# IMU.net
KiCad netlist of a schematic drawn in Altium Designer
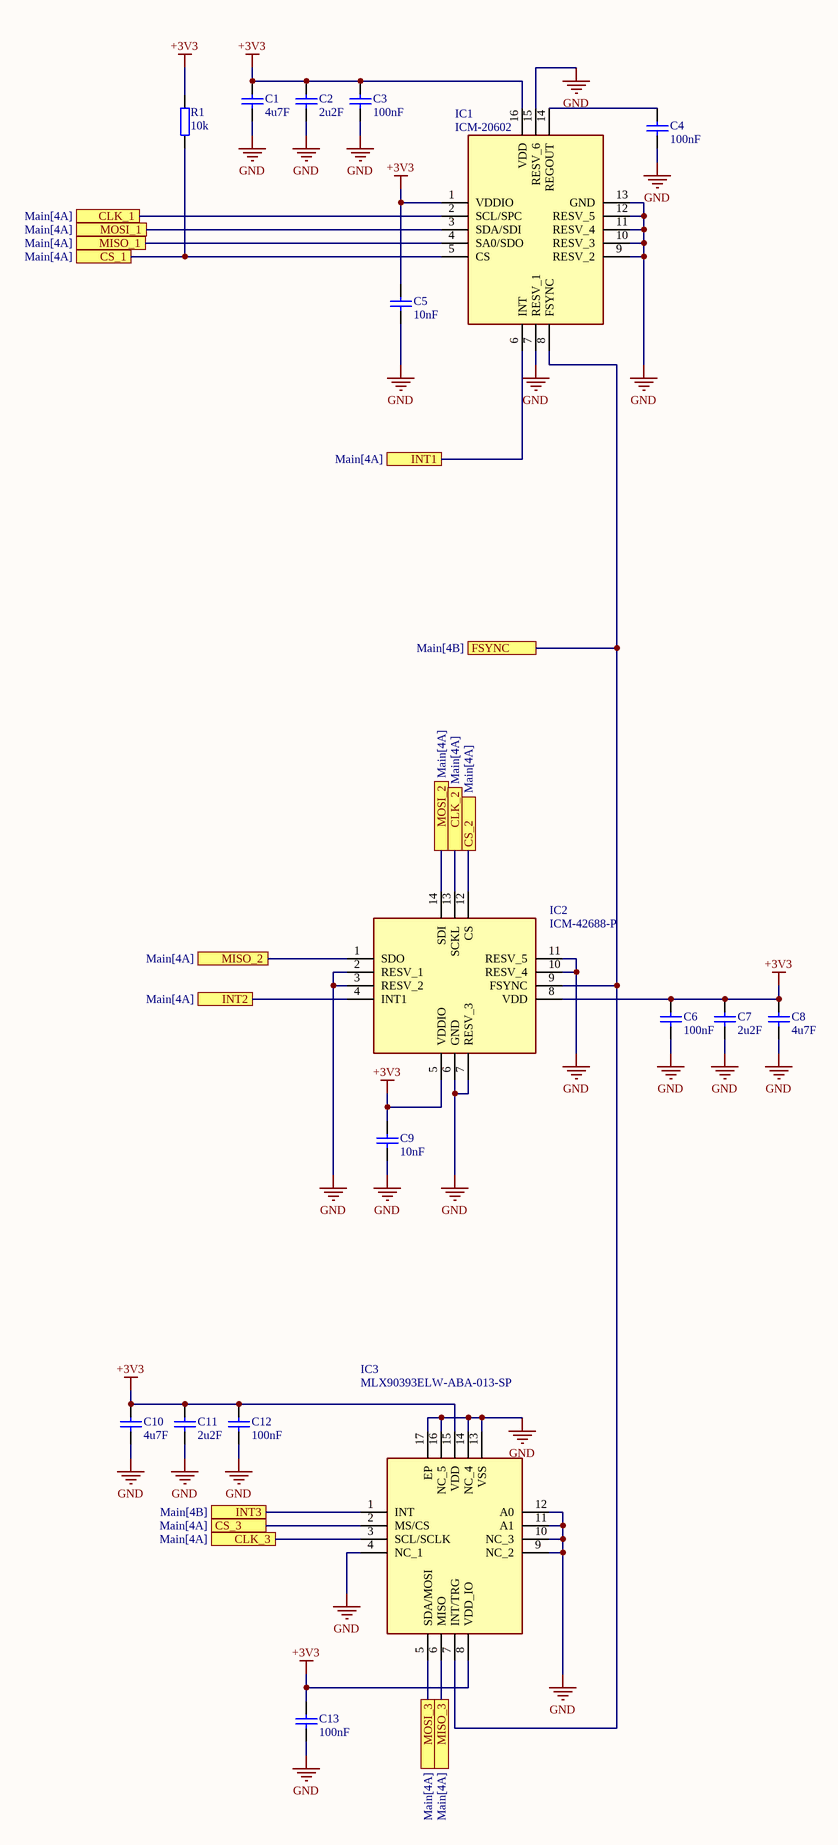
[diagram p0: IMU.SchDoc]

(export (version "E")
  (design (tool "Eeschema 10.0.6"))
  (components
    (comp (ref "C1")
      (value "4u7F")
      (footprint "CAP0805")
      (fields (field (name "VOLTAGE") "35V") (field (name "Comment") "Cap0805"))
      (libsource (lib "capacitorsSMD") (part "Cap0805"))
    )
    (comp (ref "C2")
      (value "2u2F")
      (footprint "CAP0603")
      (fields (field (name "VOLTAGE") "50V") (field (name "Comment") "Cap0603"))
      (libsource (lib "capacitorsSMD") (part "Cap0603"))
    )
    (comp (ref "C3")
      (value "100nF")
      (footprint "CAP0402")
      (fields (field (name "VOLTAGE") "50V") (field (name "Comment") "Cap0402"))
      (libsource (lib "capacitorsSMD") (part "Cap0402"))
    )
    (comp (ref "C4")
      (value "100nF")
      (footprint "CAP0402")
      (fields (field (name "VOLTAGE") "50V") (field (name "Comment") "Cap0402"))
      (libsource (lib "capacitorsSMD") (part "Cap0402"))
    )
    (comp (ref "C5")
      (value "10nF")
      (footprint "CAP0402")
      (fields (field (name "VOLTAGE") "50V") (field (name "Comment") "Cap0402"))
      (libsource (lib "capacitorsSMD") (part "Cap0402"))
    )
    (comp (ref "C6")
      (value "100nF")
      (footprint "CAP0402")
      (fields (field (name "VOLTAGE") "50V") (field (name "Comment") "Cap0402"))
      (libsource (lib "capacitorsSMD") (part "Cap0402"))
    )
    (comp (ref "C7")
      (value "2u2F")
      (footprint "CAP0603")
      (fields (field (name "VOLTAGE") "50V") (field (name "Comment") "Cap0603"))
      (libsource (lib "capacitorsSMD") (part "Cap0603"))
    )
    (comp (ref "C8")
      (value "4u7F")
      (footprint "CAP0805")
      (fields (field (name "VOLTAGE") "35V") (field (name "Comment") "Cap0805"))
      (libsource (lib "capacitorsSMD") (part "Cap0805"))
    )
    (comp (ref "C9")
      (value "10nF")
      (footprint "CAP0402")
      (fields (field (name "VOLTAGE") "50V") (field (name "Comment") "Cap0402"))
      (libsource (lib "capacitorsSMD") (part "Cap0402"))
    )
    (comp (ref "C10")
      (value "4u7F")
      (footprint "CAP0805")
      (fields (field (name "VOLTAGE") "35V") (field (name "Comment") "Cap0805"))
      (libsource (lib "capacitorsSMD") (part "Cap0805"))
    )
    (comp (ref "C11")
      (value "2u2F")
      (footprint "CAP0603")
      (fields (field (name "VOLTAGE") "50V") (field (name "Comment") "Cap0603"))
      (libsource (lib "capacitorsSMD") (part "Cap0603"))
    )
    (comp (ref "C12")
      (value "100nF")
      (footprint "CAP0402")
      (fields (field (name "VOLTAGE") "50V") (field (name "Comment") "Cap0402"))
      (libsource (lib "capacitorsSMD") (part "Cap0402"))
    )
    (comp (ref "C13")
      (value "100nF")
      (footprint "CAP0402")
      (fields (field (name "VOLTAGE") "50V") (field (name "Comment") "Cap0402"))
      (libsource (lib "capacitorsSMD") (part "Cap0402"))
    )
    (comp (ref "IC1")
      (value "ICM-20602")
      (footprint "SamacSys:IAM20680HP")
      (description "Integrated Circuit")
      (fields (field (name "MOUSER PART NUMBER") "410-ICM-20602"))
      (libsource (lib "*") (part "ICM-20602"))
    )
    (comp (ref "IC2")
      (value "ICM-42688-P")
      (footprint "SamacSys:IIM42352")
      (description "Integrated Circuit")
      (fields (field (name "MOUSER PART NUMBER") "410-ICM-42688-P"))
      (libsource (lib "SamacSys") (part "ICM-42688-P"))
    )
    (comp (ref "IC3")
      (value "MLX90393ELW-ABA-013-SP")
      (footprint "SamacSys:QFN50P300X300X100-17N-D")
      (description "Integrated Circuit")
      (fields (field (name "MOUSER PART NUMBER") "482-90393ELWABA013SP"))
      (libsource (lib "*") (part "MLX90393ELW-ABA-013-SP"))
    )
    (comp (ref "R1")
      (value "10k")
      (footprint "RES0402")
      (fields (field (name "Comment") "Res0402"))
      (libsource (lib "resistorSMD") (part "Res0402"))
    )
  )
  (nets
    (net (code "1") (name "+3V3") (class "Default")
      (node (ref "C1") (pin "2") (pinfunction "2_2") (pintype "passive"))
      (node (ref "C10") (pin "2") (pinfunction "2_2") (pintype "passive"))
      (node (ref "C11") (pin "2") (pinfunction "2_2") (pintype "passive"))
      (node (ref "C12") (pin "2") (pinfunction "2_2") (pintype "passive"))
      (node (ref "C13") (pin "2") (pinfunction "2_2") (pintype "passive"))
      (node (ref "C2") (pin "2") (pinfunction "2_2") (pintype "passive"))
      (node (ref "C3") (pin "2") (pinfunction "2_2") (pintype "passive"))
      (node (ref "C5") (pin "2") (pinfunction "2_2") (pintype "passive"))
      (node (ref "C6") (pin "2") (pinfunction "2_2") (pintype "passive"))
      (node (ref "C7") (pin "2") (pinfunction "2_2") (pintype "passive"))
      (node (ref "C8") (pin "2") (pinfunction "2_2") (pintype "passive"))
      (node (ref "C9") (pin "2") (pinfunction "2_2") (pintype "passive"))
      (node (ref "IC1") (pin "1") (pinfunction "VDDIO_1") (pintype "passive"))
      (node (ref "IC1") (pin "16") (pinfunction "VDD_16") (pintype "passive"))
      (node (ref "IC2") (pin "5") (pinfunction "VDDIO_5") (pintype "passive"))
      (node (ref "IC2") (pin "8") (pinfunction "VDD_8") (pintype "passive"))
      (node (ref "IC3") (pin "15") (pinfunction "VDD_15") (pintype "passive"))
      (node (ref "IC3") (pin "8") (pinfunction "VDD_IO_8") (pintype "passive"))
      (node (ref "R1") (pin "2") (pinfunction "2_2") (pintype "passive"))
    )
    (net (code "2") (name "/CLK_1") (class "Default")
      (node (ref "IC1") (pin "2") (pinfunction "SCL/SPC_2") (pintype "passive"))
    )
    (net (code "3") (name "/CLK_2") (class "Default")
      (node (ref "IC2") (pin "13") (pinfunction "SCKL_13") (pintype "passive"))
    )
    (net (code "4") (name "/CLK_3") (class "Default")
      (node (ref "IC3") (pin "3") (pinfunction "SCL/SCLK_3") (pintype "passive"))
    )
    (net (code "5") (name "/CS_1") (class "Default")
      (node (ref "IC1") (pin "5") (pinfunction "CS_5") (pintype "passive"))
      (node (ref "R1") (pin "1") (pinfunction "1_1") (pintype "passive"))
    )
    (net (code "6") (name "/CS_2") (class "Default")
      (node (ref "IC2") (pin "12") (pinfunction "CS_12") (pintype "passive"))
    )
    (net (code "7") (name "/CS_3") (class "Default")
      (node (ref "IC3") (pin "2") (pinfunction "MS/CS_2") (pintype "passive"))
    )
    (net (code "8") (name "/FSYNC") (class "Default")
      (node (ref "IC1") (pin "8") (pinfunction "FSYNC_8") (pintype "passive"))
      (node (ref "IC2") (pin "9") (pinfunction "FSYNC_9") (pintype "passive"))
      (node (ref "IC3") (pin "7") (pinfunction "INT/TRG_7") (pintype "passive"))
    )
    (net (code "9") (name "/INT1") (class "Default")
      (node (ref "IC1") (pin "6") (pinfunction "INT_6") (pintype "passive"))
    )
    (net (code "10") (name "/INT2") (class "Default")
      (node (ref "IC2") (pin "4") (pinfunction "INT1_4") (pintype "passive"))
    )
    (net (code "11") (name "/INT3") (class "Default")
      (node (ref "IC3") (pin "1") (pinfunction "INT_1") (pintype "passive"))
    )
    (net (code "12") (name "/MISO_1") (class "Default")
      (node (ref "IC1") (pin "4") (pinfunction "SA0/SDO_4") (pintype "passive"))
    )
    (net (code "13") (name "/MISO_2") (class "Default")
      (node (ref "IC2") (pin "1") (pinfunction "SDO_1") (pintype "passive"))
    )
    (net (code "14") (name "/MISO_3") (class "Default")
      (node (ref "IC3") (pin "6") (pinfunction "MISO_6") (pintype "passive"))
    )
    (net (code "15") (name "/MOSI_1") (class "Default")
      (node (ref "IC1") (pin "3") (pinfunction "SDA/SDI_3") (pintype "passive"))
    )
    (net (code "16") (name "/MOSI_2") (class "Default")
      (node (ref "IC2") (pin "14") (pinfunction "SDI_14") (pintype "passive"))
    )
    (net (code "17") (name "/MOSI_3") (class "Default")
      (node (ref "IC3") (pin "5") (pinfunction "SDA/MOSI_5") (pintype "passive"))
    )
    (net (code "18") (name "GND") (class "Default")
      (node (ref "C1") (pin "1") (pinfunction "1_1") (pintype "passive"))
      (node (ref "C10") (pin "1") (pinfunction "1_1") (pintype "passive"))
      (node (ref "C11") (pin "1") (pinfunction "1_1") (pintype "passive"))
      (node (ref "C12") (pin "1") (pinfunction "1_1") (pintype "passive"))
      (node (ref "C13") (pin "1") (pinfunction "1_1") (pintype "passive"))
      (node (ref "C2") (pin "1") (pinfunction "1_1") (pintype "passive"))
      (node (ref "C3") (pin "1") (pinfunction "1_1") (pintype "passive"))
      (node (ref "C4") (pin "1") (pinfunction "1_1") (pintype "passive"))
      (node (ref "C5") (pin "1") (pinfunction "1_1") (pintype "passive"))
      (node (ref "C6") (pin "1") (pinfunction "1_1") (pintype "passive"))
      (node (ref "C7") (pin "1") (pinfunction "1_1") (pintype "passive"))
      (node (ref "C8") (pin "1") (pinfunction "1_1") (pintype "passive"))
      (node (ref "C9") (pin "1") (pinfunction "1_1") (pintype "passive"))
      (node (ref "IC1") (pin "10") (pinfunction "RESV_3_10") (pintype "passive"))
      (node (ref "IC1") (pin "11") (pinfunction "RESV_4_11") (pintype "passive"))
      (node (ref "IC1") (pin "12") (pinfunction "RESV_5_12") (pintype "passive"))
      (node (ref "IC1") (pin "13") (pinfunction "GND_13") (pintype "passive"))
      (node (ref "IC1") (pin "15") (pinfunction "RESV_6_15") (pintype "passive"))
      (node (ref "IC1") (pin "7") (pinfunction "RESV_1_7") (pintype "passive"))
      (node (ref "IC1") (pin "9") (pinfunction "RESV_2_9") (pintype "passive"))
      (node (ref "IC2") (pin "10") (pinfunction "RESV_4_10") (pintype "passive"))
      (node (ref "IC2") (pin "11") (pinfunction "RESV_5_11") (pintype "passive"))
      (node (ref "IC2") (pin "2") (pinfunction "RESV_1_2") (pintype "passive"))
      (node (ref "IC2") (pin "3") (pinfunction "RESV_2_3") (pintype "passive"))
      (node (ref "IC2") (pin "6") (pinfunction "GND_6") (pintype "passive"))
      (node (ref "IC2") (pin "7") (pinfunction "RESV_3_7") (pintype "passive"))
      (node (ref "IC3") (pin "10") (pinfunction "NC_3_10") (pintype "passive"))
      (node (ref "IC3") (pin "11") (pinfunction "A1_11") (pintype "passive"))
      (node (ref "IC3") (pin "12") (pinfunction "A0_12") (pintype "passive"))
      (node (ref "IC3") (pin "13") (pinfunction "VSS_13") (pintype "passive"))
      (node (ref "IC3") (pin "14") (pinfunction "NC_4_14") (pintype "passive"))
      (node (ref "IC3") (pin "16") (pinfunction "NC_5_16") (pintype "passive"))
      (node (ref "IC3") (pin "17") (pinfunction "EP_17") (pintype "passive"))
      (node (ref "IC3") (pin "4") (pinfunction "NC_1_4") (pintype "passive"))
      (node (ref "IC3") (pin "9") (pinfunction "NC_2_9") (pintype "passive"))
    )
    (net (code "19") (name "Net-(IC1-REGOUT)") (class "Default")
      (node (ref "C4") (pin "2") (pinfunction "2_2") (pintype "passive"))
      (node (ref "IC1") (pin "14") (pinfunction "REGOUT_14") (pintype "passive"))
    )
  )
)
